# Display_Segmental_LCD118x1_DF700543-05_B.net
KiCad netlist of a schematic drawn in Altium Designer
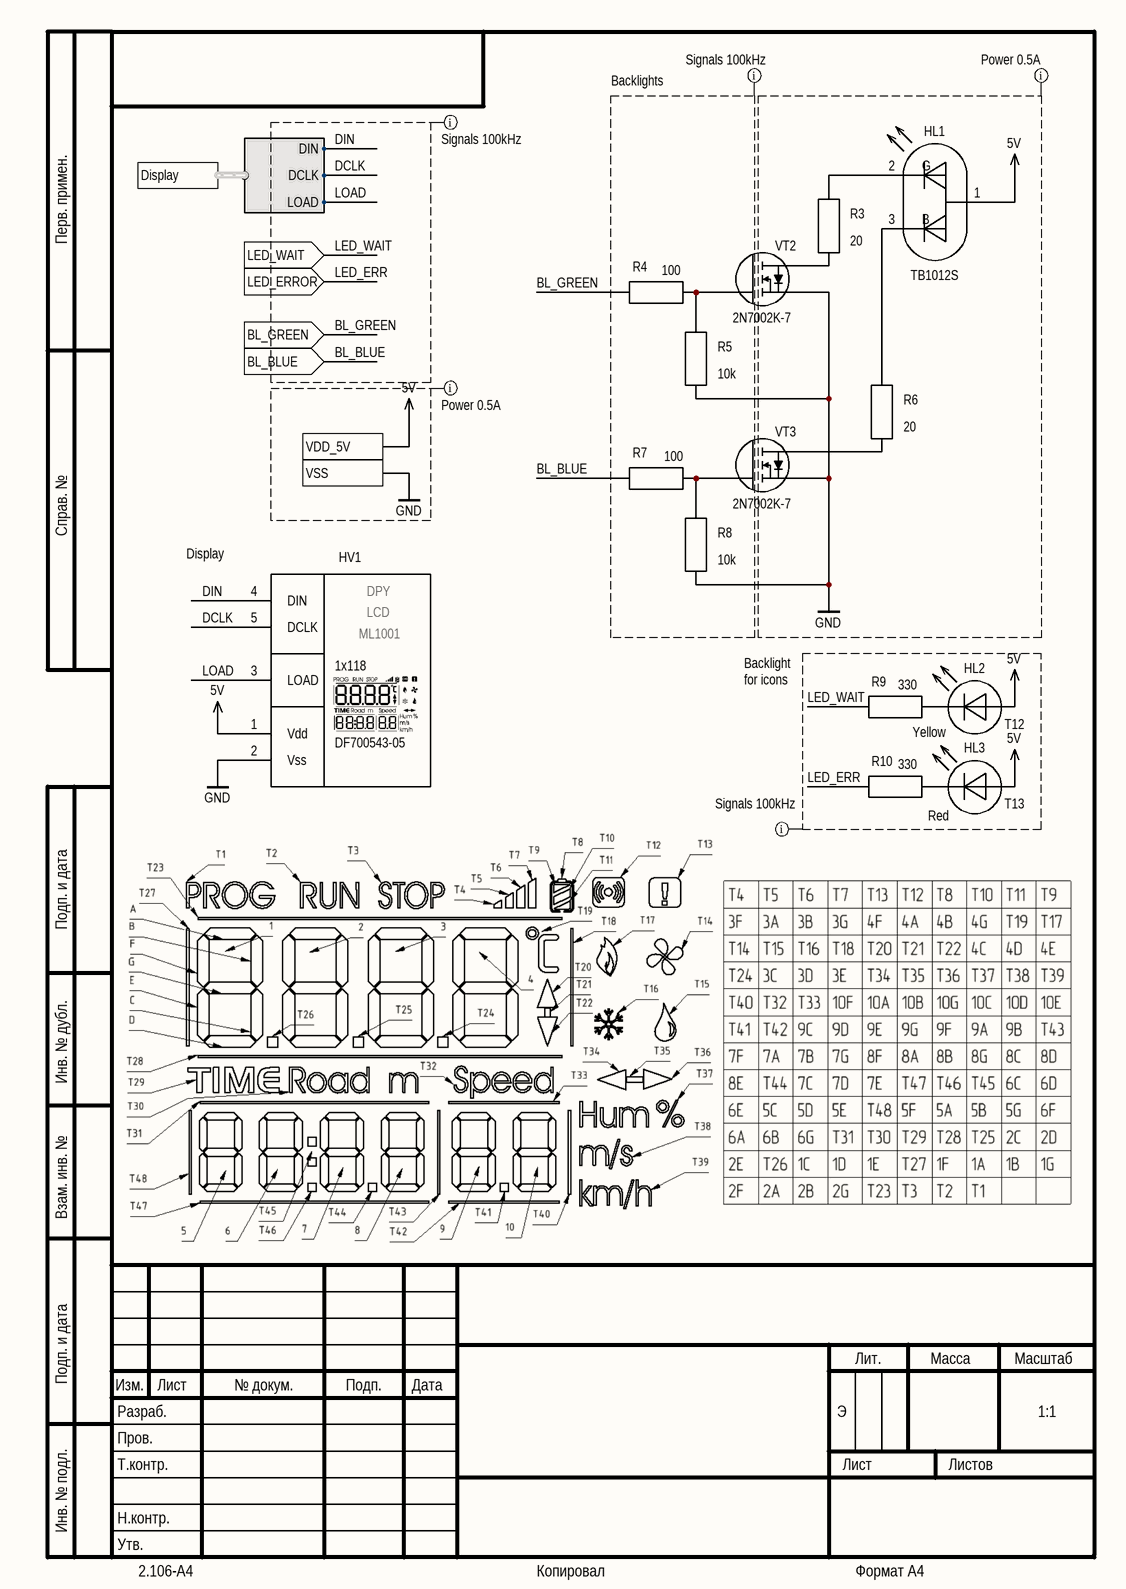
[diagram p0: Display Segmental LCD118x1 DF700543-05 Backlight TB1012S.SchDoc]

(export (version "E")
  (design (tool "Eeschema 10.0.6"))
  (components
    (comp (ref "HL1")
      (value "TB1012S")
      (footprint "DISP BKL LED TB1012S")
      (description "Display Backlight LED GB CA")
      (libsource (lib "Displays") (part "TB1012S"))
    )
    (comp (ref "HL2")
      (value "Yellow")
      (footprint "LEDD3TBN")
      (description "LED Yellow TH D3mm")
      (fields (field (name "MANUFACTURER") "Lite-On"))
      (libsource (lib "LED") (part "LTL-4251"))
    )
    (comp (ref "HL3")
      (value "Red")
      (footprint "LEDD3TBN")
      (description "LED Red TH D3mm")
      (fields (field (name "MANUFACTURER") "Lite-On"))
      (libsource (lib "LED") (part "LTL-4211"))
    )
    (comp (ref "HV1")
      (value "DF700543-05")
      (footprint "DISP SEG LCD128 DF700543-05")
      (description "Display Segmental LCD128 Special")
      (libsource (lib "Displays") (part "DF700543-05"))
    )
    (comp (ref "R3")
      (value "20")
      (footprint "RESC3225N")
      (description "RESC 20 1210(3225)")
      (fields (field (name "MANUFACTURER") "Yageo") (field (name "TOLERANCE") "±1%"))
      (libsource (lib "Resistors Ceramic SMD") (part "RC1210JR-0720RL"))
    )
    (comp (ref "R4")
      (value "100")
      (footprint "RESC2012N")
      (description "RESC 100 0805(2012)")
      (fields (field (name "MANUFACTURER") "Yageo") (field (name "TOLERANCE") "±5%"))
      (libsource (lib "Resistors Ceramic SMD 2012") (part "RC0805JR-07100RL"))
    )
    (comp (ref "R5")
      (value "10k")
      (footprint "RESC2012N")
      (description "RESC 10k 0805(2012)")
      (fields (field (name "MANUFACTURER") "Yageo") (field (name "TOLERANCE") "±5%"))
      (libsource (lib "Resistors Ceramic SMD 2012") (part "RC0805JR-0710KL"))
    )
    (comp (ref "R6")
      (value "20")
      (footprint "RESC3225N")
      (description "RESC 20 1210(3225)")
      (fields (field (name "MANUFACTURER") "Yageo") (field (name "TOLERANCE") "±1%"))
      (libsource (lib "Resistors Ceramic SMD") (part "RC1210JR-0720RL"))
    )
    (comp (ref "R7")
      (value "100")
      (footprint "RESC2012N")
      (description "RESC 100 0805(2012)")
      (fields (field (name "MANUFACTURER") "Yageo") (field (name "TOLERANCE") "±5%"))
      (libsource (lib "Resistors Ceramic SMD 2012") (part "RC0805JR-07100RL"))
    )
    (comp (ref "R8")
      (value "10k")
      (footprint "RESC2012N")
      (description "RESC 10k 0805(2012)")
      (fields (field (name "MANUFACTURER") "Yageo") (field (name "TOLERANCE") "±5%"))
      (libsource (lib "Resistors Ceramic SMD 2012") (part "RC0805JR-0710KL"))
    )
    (comp (ref "R9")
      (value "330")
      (footprint "RESC2012N")
      (description "RESC 330 0805(2012)")
      (fields (field (name "MANUFACTURER") "Yageo") (field (name "TOLERANCE") "±5%"))
      (libsource (lib "Resistors Ceramic SMD 2012") (part "RC0805JR-073300RL"))
    )
    (comp (ref "R10")
      (value "330")
      (footprint "RESC2012N")
      (description "RESC 330 0805(2012)")
      (fields (field (name "MANUFACTURER") "Yageo") (field (name "TOLERANCE") "±5%"))
      (libsource (lib "Resistors Ceramic SMD 2012") (part "RC0805JR-073300RL"))
    )
    (comp (ref "VT2")
      (value "2N7002K-7")
      (footprint "SOT-23-3N")
      (description "MOSFET N 0.38A 60V")
      (fields (field (name "MANUFACTURER") "Diodes Incorporated"))
      (libsource (lib "Transistors FET") (part "2N7002K-7"))
    )
    (comp (ref "VT3")
      (value "2N7002K-7")
      (footprint "SOT-23-3N")
      (description "MOSFET N 0.38A 60V")
      (fields (field (name "MANUFACTURER") "Diodes Incorporated"))
      (libsource (lib "Transistors FET") (part "2N7002K-7"))
    )
  )
  (nets
    (net (code "2") (name "/BL_BLUE") (class "Default")
      (node (ref "R7") (pin "1") (pinfunction "1_1") (pintype "passive"))
    )
    (net (code "3") (name "/BL_GREEN") (class "Default")
      (node (ref "R4") (pin "1") (pinfunction "1_1") (pintype "passive"))
    )
    (net (code "4") (name "/DCLK") (class "Default")
      (node (ref "HV1") (pin "5") (pinfunction "DCLK_5") (pintype "passive"))
    )
    (net (code "5") (name "/DIN") (class "Default")
      (node (ref "HV1") (pin "4") (pinfunction "DIN_4") (pintype "passive"))
    )
    (net (code "6") (name "/LED_ERR") (class "Default")
      (node (ref "R10") (pin "1") (pinfunction "1_1") (pintype "passive"))
    )
    (net (code "7") (name "/LED_WAIT") (class "Default")
      (node (ref "R9") (pin "1") (pinfunction "1_1") (pintype "passive"))
    )
    (net (code "8") (name "/LOAD") (class "Default")
      (node (ref "HV1") (pin "3") (pinfunction "LOAD_3") (pintype "passive"))
    )
    (net (code "10") (name "5V") (class "Default")
      (node (ref "HL1") (pin "1") (pinfunction "CA_1") (pintype "passive"))
      (node (ref "HL2") (pin "1") (pinfunction "Anode_1") (pintype "passive"))
      (node (ref "HL3") (pin "1") (pinfunction "Anode_1") (pintype "passive"))
      (node (ref "HV1") (pin "1") (pinfunction "Vdd_1") (pintype "passive"))
    )
    (net (code "11") (name "GND") (class "Default")
      (node (ref "HV1") (pin "2") (pinfunction "Vss_2") (pintype "passive"))
      (node (ref "R5") (pin "2") (pinfunction "2_2") (pintype "passive"))
      (node (ref "R8") (pin "2") (pinfunction "2_2") (pintype "passive"))
      (node (ref "VT2") (pin "2") (pinfunction "Source_2") (pintype "passive"))
      (node (ref "VT3") (pin "2") (pinfunction "Source_2") (pintype "passive"))
    )
    (net (code "12") (name "Net-(HL1-BLUE)") (class "Default")
      (node (ref "HL1") (pin "3") (pinfunction "BLUE_3") (pintype "passive"))
      (node (ref "R6") (pin "1") (pinfunction "1_1") (pintype "passive"))
    )
    (net (code "13") (name "Net-(HL1-GREEN)") (class "Default")
      (node (ref "HL1") (pin "2") (pinfunction "GREEN_2") (pintype "passive"))
      (node (ref "R3") (pin "1") (pinfunction "1_1") (pintype "passive"))
    )
    (net (code "14") (name "Net-(HL2-Cathode)") (class "Default")
      (node (ref "HL2") (pin "2") (pinfunction "Cathode_2") (pintype "passive"))
      (node (ref "R9") (pin "2") (pinfunction "2_2") (pintype "passive"))
    )
    (net (code "15") (name "Net-(HL3-Cathode)") (class "Default")
      (node (ref "HL3") (pin "2") (pinfunction "Cathode_2") (pintype "passive"))
      (node (ref "R10") (pin "2") (pinfunction "2_2") (pintype "passive"))
    )
    (net (code "16") (name "Net-(VT2-Drain)") (class "Default")
      (node (ref "R3") (pin "2") (pinfunction "2_2") (pintype "passive"))
      (node (ref "VT2") (pin "3") (pinfunction "Drain_3") (pintype "passive"))
    )
    (net (code "17") (name "Net-(VT2-Gate)") (class "Default")
      (node (ref "R4") (pin "2") (pinfunction "2_2") (pintype "passive"))
      (node (ref "R5") (pin "1") (pinfunction "1_1") (pintype "passive"))
      (node (ref "VT2") (pin "1") (pinfunction "Gate_1") (pintype "passive"))
    )
    (net (code "18") (name "Net-(VT3-Drain)") (class "Default")
      (node (ref "R6") (pin "2") (pinfunction "2_2") (pintype "passive"))
      (node (ref "VT3") (pin "3") (pinfunction "Drain_3") (pintype "passive"))
    )
    (net (code "19") (name "Net-(VT3-Gate)") (class "Default")
      (node (ref "R7") (pin "2") (pinfunction "2_2") (pintype "passive"))
      (node (ref "R8") (pin "1") (pinfunction "1_1") (pintype "passive"))
      (node (ref "VT3") (pin "1") (pinfunction "Gate_1") (pintype "passive"))
    )
  )
)
